# 03_USB.net
KiCad netlist of a schematic drawn in Altium Designer
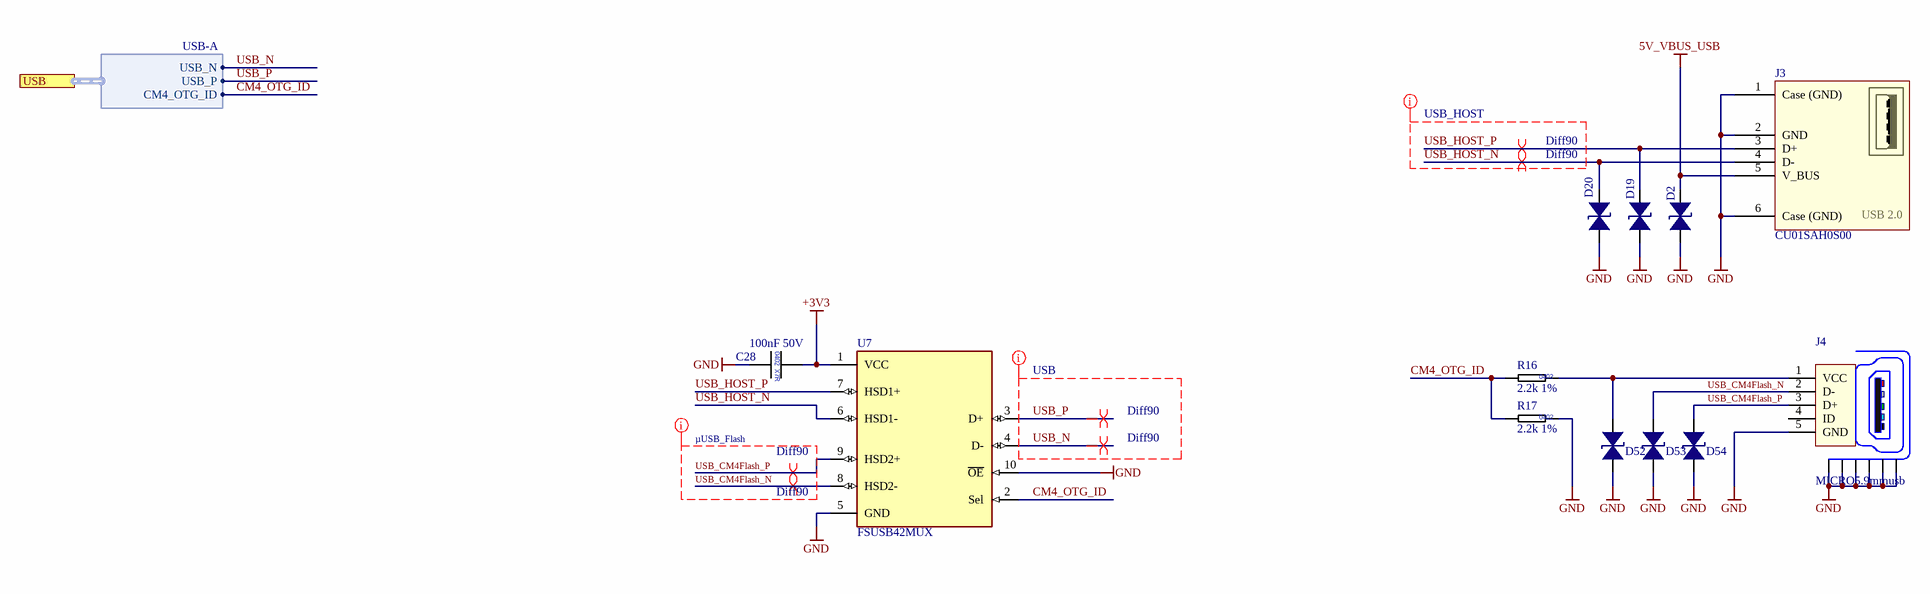
[diagram p0: 03_USB.SchDoc]

(export (version "E")
  (design (tool "Eeschema 10.0.6"))
  (components
    (comp (ref "C28")
      (value "100nF 50V")
      (footprint "Cap:CAP_0402_L")
      (description "Multilayer Ceramic Capacitors MLCC - SMD/SMT 0402 50VDC")
      (libsource (lib "Cap") (part "CAP_0402_100nF_50V"))
    )
    (comp (ref "D2")
      (value "CESDP0402UC5VB")
      (footprint "Protec:TVS_0402")
      (description "Low Capacitance ESD Protection Diode 0402")
      (libsource (lib "Protec") (part "CESDP0402UC5VB_TVS Diode 0402"))
    )
    (comp (ref "D19")
      (value "CESDP0402UC5VB")
      (footprint "Protec:TVS_0402")
      (description "Low Capacitance ESD Protection Diode 0402")
      (libsource (lib "Protec") (part "CESDP0402UC5VB_TVS Diode 0402"))
    )
    (comp (ref "D20")
      (value "CESDP0402UC5VB")
      (footprint "Protec:TVS_0402")
      (description "Low Capacitance ESD Protection Diode 0402")
      (libsource (lib "Protec") (part "CESDP0402UC5VB_TVS Diode 0402"))
    )
    (comp (ref "D52")
      (value "CESDP0402UC5VB")
      (footprint "Protec:TVS_0402")
      (description "Low Capacitance ESD Protection Diode 0402")
      (libsource (lib "Protec") (part "CESDP0402UC5VB_TVS Diode 0402"))
    )
    (comp (ref "D53")
      (value "CESDP0402UC5VB")
      (footprint "Protec:TVS_0402")
      (description "Low Capacitance ESD Protection Diode 0402")
      (libsource (lib "Protec") (part "CESDP0402UC5VB_TVS Diode 0402"))
    )
    (comp (ref "D54")
      (value "CESDP0402UC5VB")
      (footprint "Protec:TVS_0402")
      (description "Low Capacitance ESD Protection Diode 0402")
      (libsource (lib "Protec") (part "CESDP0402UC5VB_TVS Diode 0402"))
    )
    (comp (ref "J3")
      (value "CU01SAH0S00")
      (footprint "Conn:USB_A_2.0_single")
      (description "USB-A USB 2.0 Buchse Steckverbinder, rechtwinklig")
      (libsource (lib "Conn") (part "USBA_single"))
    )
    (comp (ref "J4")
      (value "MICRO5.9mmusb")
      (footprint "Conn:MICRO5.9mmusb")
      (description "SHOU HAN  MICRO5.9mmusb")
      (libsource (lib "Conn") (part "SMD micro USB Connector Horizontal C393940"))
    )
    (comp (ref "R16")
      (value "2.2k 1%")
      (footprint "Res:RES_0402_L")
      (description "Thick Film Resistors - SMD 2.2kOhm 1%")
      (libsource (lib "Res") (part "RES_0402_2.2k_1%"))
    )
    (comp (ref "R17")
      (value "2.2k 1%")
      (footprint "Res:RES_0402_L")
      (description "Thick Film Resistors - SMD 2.2kOhm 1%")
      (libsource (lib "Res") (part "RES_0402_2.2k_1%"))
    )
    (comp (ref "U7")
      (value "FSUSB42MUX")
      (footprint "digital:SOP50P300X300X110-10N")
      (description "IC USB SWITCH DPDT")
      (libsource (lib "Digital") (part "FSUSB42MUX_IC USB SWITCH DPDT"))
    )
  )
  (nets
    (net (code "2") (name "+3V3") (class "Default")
      (node (ref "C28") (pin "1") (pinfunction "1_1") (pintype "passive"))
      (node (ref "U7") (pin "1") (pinfunction "VCC_1") (pintype "power_in"))
    )
    (net (code "3") (name "/CM4_OTG_ID") (class "Default")
      (node (ref "R16") (pin "2") (pinfunction "2_2") (pintype "passive"))
      (node (ref "R17") (pin "2") (pinfunction "2_2") (pintype "passive"))
      (node (ref "U7") (pin "2") (pinfunction "Sel_2") (pintype "input"))
    )
    (net (code "4") (name "/USB_CM4Flash_N") (class "Default")
      (node (ref "D53") (pin "1") (pinfunction "1_1") (pintype "passive"))
      (node (ref "J4") (pin "2") (pinfunction "D-_2") (pintype "passive"))
      (node (ref "U7") (pin "8") (pinfunction "HSD2-_8") (pintype "bidirectional"))
    )
    (net (code "5") (name "/USB_CM4Flash_P") (class "Default")
      (node (ref "D54") (pin "1") (pinfunction "1_1") (pintype "passive"))
      (node (ref "J4") (pin "3") (pinfunction "D+_3") (pintype "passive"))
      (node (ref "U7") (pin "9") (pinfunction "HSD2+_9") (pintype "bidirectional"))
    )
    (net (code "6") (name "/USB_HOST_N") (class "Default")
      (node (ref "D20") (pin "1") (pinfunction "1_1") (pintype "passive"))
      (node (ref "J3") (pin "4") (pinfunction "D-_4") (pintype "passive"))
      (node (ref "U7") (pin "6") (pinfunction "HSD1-_6") (pintype "bidirectional"))
    )
    (net (code "7") (name "/USB_HOST_P") (class "Default")
      (node (ref "D19") (pin "1") (pinfunction "1_1") (pintype "passive"))
      (node (ref "J3") (pin "3") (pinfunction "D+_3") (pintype "passive"))
      (node (ref "U7") (pin "7") (pinfunction "HSD1+_7") (pintype "bidirectional"))
    )
    (net (code "8") (name "/USB_N") (class "Default")
      (node (ref "U7") (pin "4") (pinfunction "D-_4") (pintype "bidirectional"))
    )
    (net (code "9") (name "/USB_P") (class "Default")
      (node (ref "U7") (pin "3") (pinfunction "D+_3") (pintype "bidirectional"))
    )
    (net (code "11") (name "5V_VBUS_USB") (class "Default")
      (node (ref "D2") (pin "1") (pinfunction "1_1") (pintype "passive"))
      (node (ref "J3") (pin "5") (pinfunction "V_BUS_5") (pintype "passive"))
    )
    (net (code "12") (name "GND") (class "Default")
      (node (ref "C28") (pin "2") (pinfunction "2_2") (pintype "passive"))
      (node (ref "D19") (pin "2") (pinfunction "2_2") (pintype "passive"))
      (node (ref "D2") (pin "2") (pinfunction "2_2") (pintype "passive"))
      (node (ref "D20") (pin "2") (pinfunction "2_2") (pintype "passive"))
      (node (ref "D52") (pin "2") (pinfunction "2_2") (pintype "passive"))
      (node (ref "D53") (pin "2") (pinfunction "2_2") (pintype "passive"))
      (node (ref "D54") (pin "2") (pinfunction "2_2") (pintype "passive"))
      (node (ref "J3") (pin "1") (pinfunction "Case_(GND)_1") (pintype "passive"))
      (node (ref "J3") (pin "2") (pinfunction "GND_2") (pintype "passive"))
      (node (ref "J3") (pin "6") (pinfunction "Case_(GND)_6") (pintype "passive"))
      (node (ref "J4") (pin "10") (pinfunction "Shield_10") (pintype "passive"))
      (node (ref "J4") (pin "11") (pinfunction "Shield_11") (pintype "passive"))
      (node (ref "J4") (pin "5") (pinfunction "GND_5") (pintype "passive"))
      (node (ref "J4") (pin "6") (pinfunction "Shield_6") (pintype "passive"))
      (node (ref "J4") (pin "7") (pinfunction "Shield_7") (pintype "passive"))
      (node (ref "J4") (pin "8") (pinfunction "Shield_8") (pintype "passive"))
      (node (ref "J4") (pin "9") (pinfunction "Shield_9") (pintype "passive"))
      (node (ref "R17") (pin "1") (pinfunction "1_1") (pintype "passive"))
      (node (ref "U7") (pin "10") (pinfunction "~{OE}_10") (pintype "input"))
      (node (ref "U7") (pin "5") (pinfunction "GND_5") (pintype "power_in"))
    )
    (net (code "13") (name "Net-(J4-VCC)") (class "Default")
      (node (ref "D52") (pin "1") (pinfunction "1_1") (pintype "passive"))
      (node (ref "J4") (pin "1") (pinfunction "VCC_1") (pintype "passive"))
      (node (ref "R16") (pin "1") (pinfunction "1_1") (pintype "passive"))
    )
    (net (code "14") (name "unconnected-(J4-ID-Pad4)") (class "Default")
      (node (ref "J4") (pin "4") (pinfunction "ID_4") (pintype "passive"))
    )
  )
)
